# blm_ctrl_power.net
KiCad netlist of a schematic drawn in Altium Designer
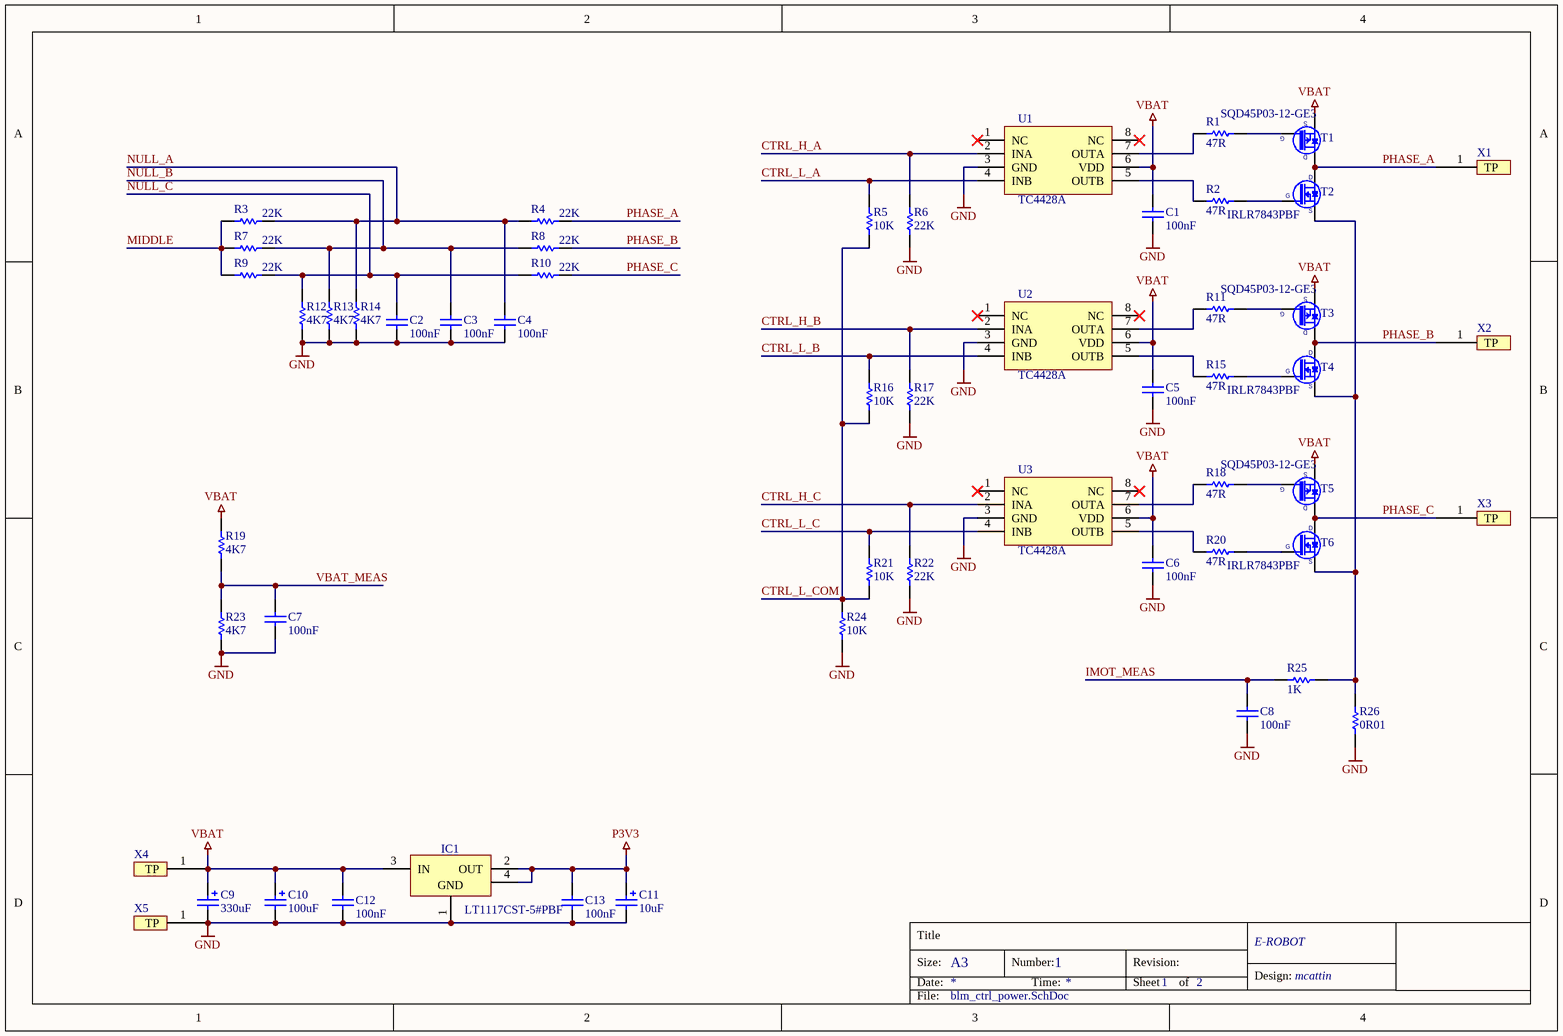
[diagram p0: blm_ctrl_power.SchDoc]

(export (version "E")
  (design (tool "Eeschema 10.0.6"))
  (components
    (comp (ref "C1")
      (value "100nF")
      (footprint "0603")
      (description "Capacitor")
      (fields (field (name "Comment") "Cap"))
      (libsource (lib "Miscellaneous Devices") (part "Cap"))
    )
    (comp (ref "C2")
      (value "100nF")
      (footprint "0603")
      (description "Capacitor")
      (fields (field (name "Comment") "Cap"))
      (libsource (lib "Miscellaneous Devices") (part "Cap"))
    )
    (comp (ref "C3")
      (value "100nF")
      (footprint "0603")
      (description "Capacitor")
      (fields (field (name "Comment") "Cap"))
      (libsource (lib "Miscellaneous Devices") (part "Cap"))
    )
    (comp (ref "C4")
      (value "100nF")
      (footprint "0603")
      (description "Capacitor")
      (fields (field (name "Comment") "Cap"))
      (libsource (lib "Miscellaneous Devices") (part "Cap"))
    )
    (comp (ref "C5")
      (value "100nF")
      (footprint "0603")
      (description "Capacitor")
      (fields (field (name "Comment") "Cap"))
      (libsource (lib "Miscellaneous Devices") (part "Cap"))
    )
    (comp (ref "C6")
      (value "100nF")
      (footprint "0603")
      (description "Capacitor")
      (fields (field (name "Comment") "Cap"))
      (libsource (lib "Miscellaneous Devices") (part "Cap"))
    )
    (comp (ref "C7")
      (value "100nF")
      (footprint "0603")
      (description "Capacitor")
      (fields (field (name "Comment") "Cap"))
      (libsource (lib "Miscellaneous Devices") (part "Cap"))
    )
    (comp (ref "C8")
      (value "100nF")
      (footprint "0603")
      (description "Capacitor")
      (fields (field (name "Comment") "Cap"))
      (libsource (lib "Miscellaneous Devices") (part "Cap"))
    )
    (comp (ref "C9")
      (value "330uF")
      (footprint "C00101")
      (description "Polarized Capacitor (Axial)")
      (fields (field (name "Comment") "Cap Pol2"))
      (libsource (lib "Miscellaneous Devices") (part "Cap Pol2"))
    )
    (comp (ref "C10")
      (value "100uF")
      (footprint "C00101")
      (description "Polarized Capacitor (Axial)")
      (fields (field (name "Comment") "Cap Pol2"))
      (libsource (lib "Miscellaneous Devices") (part "Cap Pol2"))
    )
    (comp (ref "C11")
      (value "10uF")
      (footprint "1206")
      (description "Polarized Capacitor (Axial)")
      (fields (field (name "Comment") "Cap Pol2"))
      (libsource (lib "Miscellaneous Devices") (part "Cap Pol2"))
    )
    (comp (ref "C12")
      (value "100nF")
      (footprint "0603")
      (description "Capacitor")
      (fields (field (name "Comment") "Cap"))
      (libsource (lib "Miscellaneous Devices") (part "Cap"))
    )
    (comp (ref "C13")
      (value "100nF")
      (footprint "0603")
      (description "Capacitor")
      (fields (field (name "Comment") "Cap"))
      (libsource (lib "Miscellaneous Devices") (part "Cap"))
    )
    (comp (ref "IC1")
      (value "LT1117CST-5#PBF")
      (footprint "SOT230P700X180-4N")
      (description "3-Terminal Regulator 1=GND 2=OUT 3=IN 4=OUT")
      (fields (field (name "MANUFACTURER") "LINEAR TECHNOLOGY"))
      (libsource (lib "ICs And Semiconductors") (part "REG3+1 1GND-2OUT-3IN+4OUT"))
    )
    (comp (ref "R1")
      (value "47R")
      (footprint "0603")
      (description "Resistor")
      (fields (field (name "Comment") "Res1"))
      (libsource (lib "Miscellaneous Devices") (part "Res1"))
    )
    (comp (ref "R2")
      (value "47R")
      (footprint "0603")
      (description "Resistor")
      (fields (field (name "Comment") "Res1"))
      (libsource (lib "Miscellaneous Devices") (part "Res1"))
    )
    (comp (ref "R3")
      (value "22K")
      (footprint "0603")
      (description "Resistor")
      (fields (field (name "Comment") "Res1"))
      (libsource (lib "Miscellaneous Devices") (part "Res1"))
    )
    (comp (ref "R4")
      (value "22K")
      (footprint "0603")
      (description "Resistor")
      (fields (field (name "Comment") "Res1"))
      (libsource (lib "Miscellaneous Devices") (part "Res1"))
    )
    (comp (ref "R5")
      (value "10K")
      (footprint "0603")
      (description "Resistor")
      (fields (field (name "Comment") "Res1"))
      (libsource (lib "Miscellaneous Devices") (part "Res1"))
    )
    (comp (ref "R6")
      (value "22K")
      (footprint "0603")
      (description "Resistor")
      (fields (field (name "Comment") "Res1"))
      (libsource (lib "Miscellaneous Devices") (part "Res1"))
    )
    (comp (ref "R7")
      (value "22K")
      (footprint "0603")
      (description "Resistor")
      (fields (field (name "Comment") "Res1"))
      (libsource (lib "Miscellaneous Devices") (part "Res1"))
    )
    (comp (ref "R8")
      (value "22K")
      (footprint "0603")
      (description "Resistor")
      (fields (field (name "Comment") "Res1"))
      (libsource (lib "Miscellaneous Devices") (part "Res1"))
    )
    (comp (ref "R9")
      (value "22K")
      (footprint "0603")
      (description "Resistor")
      (fields (field (name "Comment") "Res1"))
      (libsource (lib "Miscellaneous Devices") (part "Res1"))
    )
    (comp (ref "R10")
      (value "22K")
      (footprint "0603")
      (description "Resistor")
      (fields (field (name "Comment") "Res1"))
      (libsource (lib "Miscellaneous Devices") (part "Res1"))
    )
    (comp (ref "R11")
      (value "47R")
      (footprint "0603")
      (description "Resistor")
      (fields (field (name "Comment") "Res1"))
      (libsource (lib "Miscellaneous Devices") (part "Res1"))
    )
    (comp (ref "R12")
      (value "4K7")
      (footprint "0603")
      (description "Resistor")
      (fields (field (name "Comment") "Res1"))
      (libsource (lib "Miscellaneous Devices") (part "Res1"))
    )
    (comp (ref "R13")
      (value "4K7")
      (footprint "0603")
      (description "Resistor")
      (fields (field (name "Comment") "Res1"))
      (libsource (lib "Miscellaneous Devices") (part "Res1"))
    )
    (comp (ref "R14")
      (value "4K7")
      (footprint "0603")
      (description "Resistor")
      (fields (field (name "Comment") "Res1"))
      (libsource (lib "Miscellaneous Devices") (part "Res1"))
    )
    (comp (ref "R15")
      (value "47R")
      (footprint "0603")
      (description "Resistor")
      (fields (field (name "Comment") "Res1"))
      (libsource (lib "Miscellaneous Devices") (part "Res1"))
    )
    (comp (ref "R16")
      (value "10K")
      (footprint "0603")
      (description "Resistor")
      (fields (field (name "Comment") "Res1"))
      (libsource (lib "Miscellaneous Devices") (part "Res1"))
    )
    (comp (ref "R17")
      (value "22K")
      (footprint "0603")
      (description "Resistor")
      (fields (field (name "Comment") "Res1"))
      (libsource (lib "Miscellaneous Devices") (part "Res1"))
    )
    (comp (ref "R18")
      (value "47R")
      (footprint "0603")
      (description "Resistor")
      (fields (field (name "Comment") "Res1"))
      (libsource (lib "Miscellaneous Devices") (part "Res1"))
    )
    (comp (ref "R19")
      (value "4K7")
      (footprint "0603")
      (description "Resistor")
      (fields (field (name "Comment") "Res1"))
      (libsource (lib "Miscellaneous Devices") (part "Res1"))
    )
    (comp (ref "R20")
      (value "47R")
      (footprint "0603")
      (description "Resistor")
      (fields (field (name "Comment") "Res1"))
      (libsource (lib "Miscellaneous Devices") (part "Res1"))
    )
    (comp (ref "R21")
      (value "10K")
      (footprint "0603")
      (description "Resistor")
      (fields (field (name "Comment") "Res1"))
      (libsource (lib "Miscellaneous Devices") (part "Res1"))
    )
    (comp (ref "R22")
      (value "22K")
      (footprint "0603")
      (description "Resistor")
      (fields (field (name "Comment") "Res1"))
      (libsource (lib "Miscellaneous Devices") (part "Res1"))
    )
    (comp (ref "R23")
      (value "4K7")
      (footprint "0603")
      (description "Resistor")
      (fields (field (name "Comment") "Res1"))
      (libsource (lib "Miscellaneous Devices") (part "Res1"))
    )
    (comp (ref "R24")
      (value "10K")
      (footprint "0603")
      (description "Resistor")
      (fields (field (name "Comment") "Res1"))
      (libsource (lib "Miscellaneous Devices") (part "Res1"))
    )
    (comp (ref "R25")
      (value "1K")
      (footprint "0603")
      (description "Resistor")
      (fields (field (name "Comment") "Res1"))
      (libsource (lib "Miscellaneous Devices") (part "Res1"))
    )
    (comp (ref "R26")
      (value "0R01")
      (footprint "2512")
      (description "Resistor")
      (fields (field (name "Comment") "Res1"))
      (libsource (lib "Miscellaneous Devices") (part "Res1"))
    )
    (comp (ref "T1")
      (value "SQD45P03-12-GE3")
      (footprint "TO-252AA")
      (description "P-CHANNEL MOSFET WITH DIODE")
      (fields (field (name "MANUFACTURER") "Vishay"))
      (libsource (lib "ICs And Semiconductors") (part "P-MOSFET-D 1G 2S 3D"))
    )
    (comp (ref "T2")
      (value "IRLR7843PBF")
      (footprint "TO-252AA")
      (description "N-CHANNEL MOSFET WITH DIODE")
      (fields (field (name "MANUFACTURER") "INTERNATIONAL RECTIFIER"))
      (libsource (lib "ICs And Semiconductors") (part "N-MOSFET-D 1G 2S 3D"))
    )
    (comp (ref "T3")
      (value "SQD45P03-12-GE3")
      (footprint "TO-252AA")
      (description "P-CHANNEL MOSFET WITH DIODE")
      (fields (field (name "MANUFACTURER") "Vishay"))
      (libsource (lib "ICs And Semiconductors") (part "P-MOSFET-D 1G 2S 3D"))
    )
    (comp (ref "T4")
      (value "IRLR7843PBF")
      (footprint "TO-252AA")
      (description "N-CHANNEL MOSFET WITH DIODE")
      (fields (field (name "MANUFACTURER") "INTERNATIONAL RECTIFIER"))
      (libsource (lib "ICs And Semiconductors") (part "N-MOSFET-D 1G 2S 3D"))
    )
    (comp (ref "T5")
      (value "SQD45P03-12-GE3")
      (footprint "TO-252AA")
      (description "P-CHANNEL MOSFET WITH DIODE")
      (fields (field (name "MANUFACTURER") "Vishay"))
      (libsource (lib "ICs And Semiconductors") (part "P-MOSFET-D 1G 2S 3D"))
    )
    (comp (ref "T6")
      (value "IRLR7843PBF")
      (footprint "TO-252AA")
      (description "N-CHANNEL MOSFET WITH DIODE")
      (fields (field (name "MANUFACTURER") "INTERNATIONAL RECTIFIER"))
      (libsource (lib "ICs And Semiconductors") (part "N-MOSFET-D 1G 2S 3D"))
    )
    (comp (ref "U1")
      (value "TC4428A")
      (footprint "SOIC127P600-8BN")
      (fields (field (name "MANUFACTURER") "MICROCHIP") (field (name "PART NUMBER") "TC4428ACOA"))
      (libsource (lib "MyLibrary") (part "TC4428A"))
    )
    (comp (ref "U2")
      (value "TC4428A")
      (footprint "SOIC127P600-8BN")
      (fields (field (name "MANUFACTURER") "MICROCHIP") (field (name "PART NUMBER") "TC4428ACOA"))
      (libsource (lib "MyLibrary") (part "TC4428A"))
    )
    (comp (ref "U3")
      (value "TC4428A")
      (footprint "SOIC127P600-8BN")
      (fields (field (name "MANUFACTURER") "MICROCHIP") (field (name "PART NUMBER") "TC4428ACOA"))
      (libsource (lib "MyLibrary") (part "TC4428A"))
    )
    (comp (ref "X1")
      (value "~")
      (footprint "PAD_SMD_2x7MM")
      (libsource (lib "MyLibrary") (part "TEST_POINT"))
    )
    (comp (ref "X2")
      (value "~")
      (footprint "PAD_SMD_2x7MM")
      (libsource (lib "MyLibrary") (part "TEST_POINT"))
    )
    (comp (ref "X3")
      (value "~")
      (footprint "PAD_SMD_2x7MM")
      (libsource (lib "MyLibrary") (part "TEST_POINT"))
    )
    (comp (ref "X4") (value "~") (footprint "PAD_SMD_2x7MM") (libsource (lib "") (part "TEST_POINT_1")))
    (comp (ref "X5") (value "~") (footprint "PAD_SMD_2x7MM") (libsource (lib "") (part "TEST_POINT_1")))
  )
  (nets
    (net (code "1") (name "/CTRL_H_A") (class "Default")
      (node (ref "R6") (pin "1") (pinfunction "1_1") (pintype "passive"))
      (node (ref "U1") (pin "2") (pinfunction "INA_2") (pintype "passive"))
    )
    (net (code "2") (name "/CTRL_H_B") (class "Default")
      (node (ref "R17") (pin "1") (pinfunction "1_1") (pintype "passive"))
      (node (ref "U2") (pin "2") (pinfunction "INA_2") (pintype "passive"))
    )
    (net (code "3") (name "/CTRL_H_C") (class "Default")
      (node (ref "R22") (pin "1") (pinfunction "1_1") (pintype "passive"))
      (node (ref "U3") (pin "2") (pinfunction "INA_2") (pintype "passive"))
    )
    (net (code "4") (name "/CTRL_L_A") (class "Default")
      (node (ref "R5") (pin "1") (pinfunction "1_1") (pintype "passive"))
      (node (ref "U1") (pin "4") (pinfunction "INB_4") (pintype "passive"))
    )
    (net (code "5") (name "/CTRL_L_B") (class "Default")
      (node (ref "R16") (pin "1") (pinfunction "1_1") (pintype "passive"))
      (node (ref "U2") (pin "4") (pinfunction "INB_4") (pintype "passive"))
    )
    (net (code "6") (name "/CTRL_L_C") (class "Default")
      (node (ref "R21") (pin "1") (pinfunction "1_1") (pintype "passive"))
      (node (ref "U3") (pin "4") (pinfunction "INB_4") (pintype "passive"))
    )
    (net (code "7") (name "/CTRL_L_COM") (class "Default")
      (node (ref "R16") (pin "2") (pinfunction "2_2") (pintype "passive"))
      (node (ref "R21") (pin "2") (pinfunction "2_2") (pintype "passive"))
      (node (ref "R24") (pin "1") (pinfunction "1_1") (pintype "passive"))
      (node (ref "R5") (pin "2") (pinfunction "2_2") (pintype "passive"))
    )
    (net (code "8") (name "/IMOT_MEAS") (class "Default")
      (node (ref "C8") (pin "1") (pinfunction "1_1") (pintype "passive"))
      (node (ref "R25") (pin "2") (pinfunction "2_2") (pintype "passive"))
    )
    (net (code "9") (name "/MIDDLE") (class "Default")
      (node (ref "R3") (pin "1") (pinfunction "1_1") (pintype "passive"))
      (node (ref "R7") (pin "1") (pinfunction "1_1") (pintype "passive"))
      (node (ref "R9") (pin "1") (pinfunction "1_1") (pintype "passive"))
    )
    (net (code "10") (name "/NULL_A") (class "Default")
      (node (ref "C4") (pin "1") (pinfunction "1_1") (pintype "passive"))
      (node (ref "R14") (pin "1") (pinfunction "1_1") (pintype "passive"))
      (node (ref "R3") (pin "2") (pinfunction "2_2") (pintype "passive"))
      (node (ref "R4") (pin "1") (pinfunction "1_1") (pintype "passive"))
    )
    (net (code "11") (name "/NULL_B") (class "Default")
      (node (ref "C3") (pin "1") (pinfunction "1_1") (pintype "passive"))
      (node (ref "R13") (pin "1") (pinfunction "1_1") (pintype "passive"))
      (node (ref "R7") (pin "2") (pinfunction "2_2") (pintype "passive"))
      (node (ref "R8") (pin "1") (pinfunction "1_1") (pintype "passive"))
    )
    (net (code "12") (name "/NULL_C") (class "Default")
      (node (ref "C2") (pin "1") (pinfunction "1_1") (pintype "passive"))
      (node (ref "R10") (pin "1") (pinfunction "1_1") (pintype "passive"))
      (node (ref "R12") (pin "1") (pinfunction "1_1") (pintype "passive"))
      (node (ref "R9") (pin "2") (pinfunction "2_2") (pintype "passive"))
    )
    (net (code "13") (name "/PHASE_A") (class "Default")
      (node (ref "R4") (pin "2") (pinfunction "2_2") (pintype "passive"))
      (node (ref "T1") (pin "4") (pinfunction "D_4") (pintype "passive"))
      (node (ref "T2") (pin "4") (pinfunction "D_4") (pintype "passive"))
      (node (ref "X1") (pin "1") (pinfunction "TP_1") (pintype "passive"))
    )
    (net (code "14") (name "/PHASE_B") (class "Default")
      (node (ref "R8") (pin "2") (pinfunction "2_2") (pintype "passive"))
      (node (ref "T3") (pin "4") (pinfunction "D_4") (pintype "passive"))
      (node (ref "T4") (pin "4") (pinfunction "D_4") (pintype "passive"))
      (node (ref "X2") (pin "1") (pinfunction "TP_1") (pintype "passive"))
    )
    (net (code "15") (name "/PHASE_C") (class "Default")
      (node (ref "R10") (pin "2") (pinfunction "2_2") (pintype "passive"))
      (node (ref "T5") (pin "4") (pinfunction "D_4") (pintype "passive"))
      (node (ref "T6") (pin "4") (pinfunction "D_4") (pintype "passive"))
      (node (ref "X3") (pin "1") (pinfunction "TP_1") (pintype "passive"))
    )
    (net (code "16") (name "/VBAT_MEAS") (class "Default")
      (node (ref "C7") (pin "1") (pinfunction "1_1") (pintype "passive"))
      (node (ref "R19") (pin "2") (pinfunction "2_2") (pintype "passive"))
      (node (ref "R23") (pin "1") (pinfunction "1_1") (pintype "passive"))
    )
    (net (code "17") (name "GND") (class "Default")
      (node (ref "C1") (pin "2") (pinfunction "2_2") (pintype "passive"))
      (node (ref "C10") (pin "2") (pinfunction "2_2") (pintype "passive"))
      (node (ref "C11") (pin "2") (pinfunction "2_2") (pintype "passive"))
      (node (ref "C12") (pin "2") (pinfunction "2_2") (pintype "passive"))
      (node (ref "C13") (pin "2") (pinfunction "2_2") (pintype "passive"))
      (node (ref "C2") (pin "2") (pinfunction "2_2") (pintype "passive"))
      (node (ref "C3") (pin "2") (pinfunction "2_2") (pintype "passive"))
      (node (ref "C4") (pin "2") (pinfunction "2_2") (pintype "passive"))
      (node (ref "C5") (pin "2") (pinfunction "2_2") (pintype "passive"))
      (node (ref "C6") (pin "2") (pinfunction "2_2") (pintype "passive"))
      (node (ref "C7") (pin "2") (pinfunction "2_2") (pintype "passive"))
      (node (ref "C8") (pin "2") (pinfunction "2_2") (pintype "passive"))
      (node (ref "C9") (pin "2") (pinfunction "2_2") (pintype "passive"))
      (node (ref "IC1") (pin "1") (pinfunction "GND_1") (pintype "power_in"))
      (node (ref "R12") (pin "2") (pinfunction "2_2") (pintype "passive"))
      (node (ref "R13") (pin "2") (pinfunction "2_2") (pintype "passive"))
      (node (ref "R14") (pin "2") (pinfunction "2_2") (pintype "passive"))
      (node (ref "R17") (pin "2") (pinfunction "2_2") (pintype "passive"))
      (node (ref "R22") (pin "2") (pinfunction "2_2") (pintype "passive"))
      (node (ref "R23") (pin "2") (pinfunction "2_2") (pintype "passive"))
      (node (ref "R24") (pin "2") (pinfunction "2_2") (pintype "passive"))
      (node (ref "R26") (pin "2") (pinfunction "2_2") (pintype "passive"))
      (node (ref "R6") (pin "2") (pinfunction "2_2") (pintype "passive"))
      (node (ref "U1") (pin "3") (pinfunction "GND_3") (pintype "passive"))
      (node (ref "U2") (pin "3") (pinfunction "GND_3") (pintype "passive"))
      (node (ref "U3") (pin "3") (pinfunction "GND_3") (pintype "passive"))
      (node (ref "X5") (pin "1") (pinfunction "TP_1") (pintype "passive"))
    )
    (net (code "18") (name "Net-(T1-G)") (class "Default")
      (node (ref "R1") (pin "1") (pinfunction "1_1") (pintype "passive"))
      (node (ref "T1") (pin "1") (pinfunction "G_1") (pintype "passive"))
    )
    (net (code "19") (name "Net-(T2-G)") (class "Default")
      (node (ref "R2") (pin "1") (pinfunction "1_1") (pintype "passive"))
      (node (ref "T2") (pin "1") (pinfunction "G_1") (pintype "passive"))
    )
    (net (code "20") (name "Net-(T2-S)") (class "Default")
      (node (ref "R25") (pin "1") (pinfunction "1_1") (pintype "passive"))
      (node (ref "R26") (pin "1") (pinfunction "1_1") (pintype "passive"))
      (node (ref "T2") (pin "3") (pinfunction "S_3") (pintype "passive"))
      (node (ref "T4") (pin "3") (pinfunction "S_3") (pintype "passive"))
      (node (ref "T6") (pin "3") (pinfunction "S_3") (pintype "passive"))
    )
    (net (code "21") (name "Net-(T3-G)") (class "Default")
      (node (ref "R11") (pin "1") (pinfunction "1_1") (pintype "passive"))
      (node (ref "T3") (pin "1") (pinfunction "G_1") (pintype "passive"))
    )
    (net (code "22") (name "Net-(T4-G)") (class "Default")
      (node (ref "R15") (pin "1") (pinfunction "1_1") (pintype "passive"))
      (node (ref "T4") (pin "1") (pinfunction "G_1") (pintype "passive"))
    )
    (net (code "23") (name "Net-(T5-G)") (class "Default")
      (node (ref "R18") (pin "1") (pinfunction "1_1") (pintype "passive"))
      (node (ref "T5") (pin "1") (pinfunction "G_1") (pintype "passive"))
    )
    (net (code "24") (name "Net-(T6-G)") (class "Default")
      (node (ref "R20") (pin "1") (pinfunction "1_1") (pintype "passive"))
      (node (ref "T6") (pin "1") (pinfunction "G_1") (pintype "passive"))
    )
    (net (code "25") (name "Net-(U1-OUTA)") (class "Default")
      (node (ref "R1") (pin "2") (pinfunction "2_2") (pintype "passive"))
      (node (ref "U1") (pin "7") (pinfunction "OUTA_7") (pintype "passive"))
    )
    (net (code "26") (name "Net-(U1-OUTB)") (class "Default")
      (node (ref "R2") (pin "2") (pinfunction "2_2") (pintype "passive"))
      (node (ref "U1") (pin "5") (pinfunction "OUTB_5") (pintype "passive"))
    )
    (net (code "27") (name "Net-(U2-OUTA)") (class "Default")
      (node (ref "R11") (pin "2") (pinfunction "2_2") (pintype "passive"))
      (node (ref "U2") (pin "7") (pinfunction "OUTA_7") (pintype "passive"))
    )
    (net (code "28") (name "Net-(U2-OUTB)") (class "Default")
      (node (ref "R15") (pin "2") (pinfunction "2_2") (pintype "passive"))
      (node (ref "U2") (pin "5") (pinfunction "OUTB_5") (pintype "passive"))
    )
    (net (code "29") (name "Net-(U3-OUTA)") (class "Default")
      (node (ref "R18") (pin "2") (pinfunction "2_2") (pintype "passive"))
      (node (ref "U3") (pin "7") (pinfunction "OUTA_7") (pintype "passive"))
    )
    (net (code "30") (name "Net-(U3-OUTB)") (class "Default")
      (node (ref "R20") (pin "2") (pinfunction "2_2") (pintype "passive"))
      (node (ref "U3") (pin "5") (pinfunction "OUTB_5") (pintype "passive"))
    )
    (net (code "31") (name "P3V3") (class "Default")
      (node (ref "C11") (pin "1") (pinfunction "1_1") (pintype "passive"))
      (node (ref "C13") (pin "1") (pinfunction "1_1") (pintype "passive"))
      (node (ref "IC1") (pin "2") (pinfunction "OUT_2") (pintype "power_in"))
      (node (ref "IC1") (pin "4") (pinfunction "OUT_4") (pintype "power_in"))
    )
    (net (code "32") (name "VBAT") (class "Default")
      (node (ref "C1") (pin "1") (pinfunction "1_1") (pintype "passive"))
      (node (ref "C10") (pin "1") (pinfunction "1_1") (pintype "passive"))
      (node (ref "C12") (pin "1") (pinfunction "1_1") (pintype "passive"))
      (node (ref "C5") (pin "1") (pinfunction "1_1") (pintype "passive"))
      (node (ref "C6") (pin "1") (pinfunction "1_1") (pintype "passive"))
      (node (ref "C9") (pin "1") (pinfunction "1_1") (pintype "passive"))
      (node (ref "IC1") (pin "3") (pinfunction "IN_3") (pintype "power_in"))
      (node (ref "R19") (pin "1") (pinfunction "1_1") (pintype "passive"))
      (node (ref "T1") (pin "3") (pinfunction "S_3") (pintype "passive"))
      (node (ref "T3") (pin "3") (pinfunction "S_3") (pintype "passive"))
      (node (ref "T5") (pin "3") (pinfunction "S_3") (pintype "passive"))
      (node (ref "U1") (pin "6") (pinfunction "VDD_6") (pintype "passive"))
      (node (ref "U2") (pin "6") (pinfunction "VDD_6") (pintype "passive"))
      (node (ref "U3") (pin "6") (pinfunction "VDD_6") (pintype "passive"))
      (node (ref "X4") (pin "1") (pinfunction "TP_1") (pintype "passive"))
    )
    (net (code "33") (name "unconnected-(U1-NC-Pad1)") (class "Default")
      (node (ref "U1") (pin "1") (pinfunction "NC_1") (pintype "passive+no_connect"))
    )
    (net (code "34") (name "unconnected-(U1-NC-Pad8)") (class "Default")
      (node (ref "U1") (pin "8") (pinfunction "NC_8") (pintype "passive+no_connect"))
    )
    (net (code "35") (name "unconnected-(U2-NC-Pad1)") (class "Default")
      (node (ref "U2") (pin "1") (pinfunction "NC_1") (pintype "passive+no_connect"))
    )
    (net (code "36") (name "unconnected-(U2-NC-Pad8)") (class "Default")
      (node (ref "U2") (pin "8") (pinfunction "NC_8") (pintype "passive+no_connect"))
    )
    (net (code "37") (name "unconnected-(U3-NC-Pad1)") (class "Default")
      (node (ref "U3") (pin "1") (pinfunction "NC_1") (pintype "passive+no_connect"))
    )
    (net (code "38") (name "unconnected-(U3-NC-Pad8)") (class "Default")
      (node (ref "U3") (pin "8") (pinfunction "NC_8") (pintype "passive+no_connect"))
    )
  )
)
